# TIDM_TM4C129CAMERA.net
KiCad netlist of a schematic drawn in Altium Designer
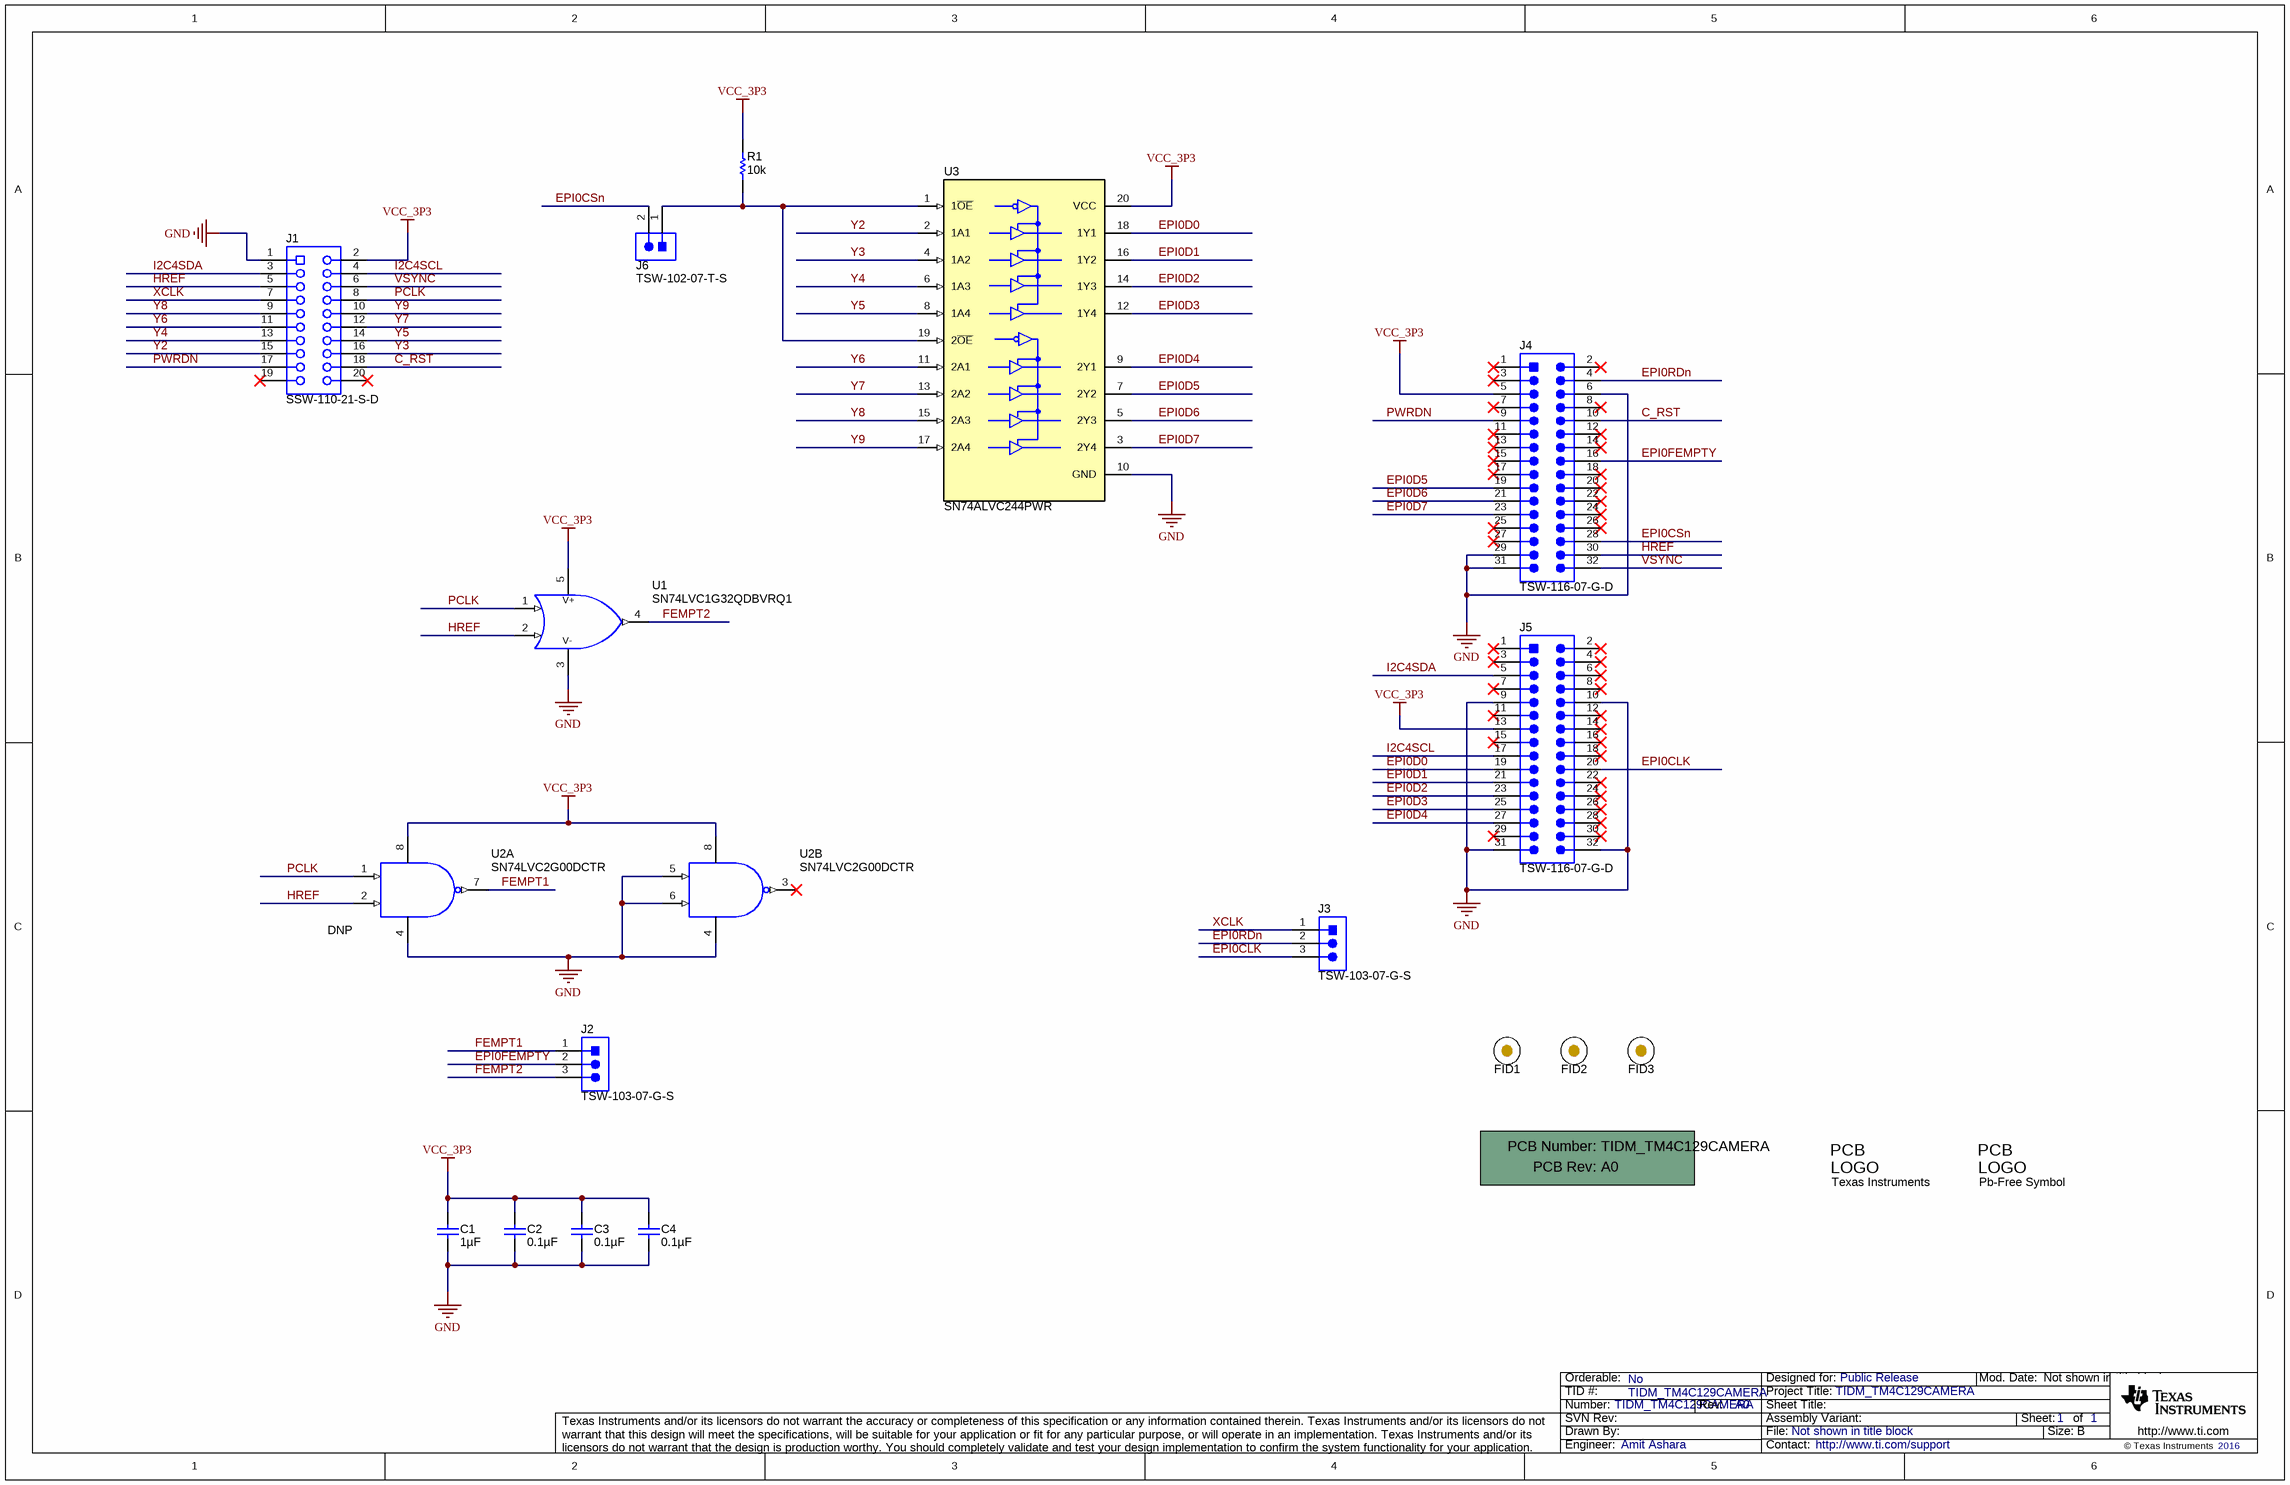
[diagram p0: TIDM_TM4C129CAMERA.SchDoc]

(export (version "E")
  (design (tool "Eeschema 10.0.6"))
  (components
    (comp (ref "!PCB")
      (value "Printed Circuit Board")
      (fields
        (field (name "MANUFACTURER") "Any")
        (field (name "SYMBOLCREATOR") "a0412235")
        (field (name "PUBLISHER") "Texas Instruments")
      )
      (libsource (lib "Hardware") (part "PCB"))
    )
    (comp (ref "C1")
      (value "GRM188R71A105KA61D")
      (footprint "0603")
      (description "CAP, CERM, 1 µF, 10 V, +/- 10%, X7R, 0603")
      (fields
        (field (name "VALUEDISPLAYED") "1µF")
        (field (name "MANUFACTURER") "MuRata")
        (field (name "PUBLISHER") "Texas Instruments")
      )
      (libsource (lib "Capacitor_Ceramic") (part "GRM188R71A105KA61D"))
    )
    (comp (ref "C2")
      (value "C0603C104K8RACTU")
      (footprint "0603")
      (description "CAP, CERM, 0.1 µF, 10 V, +/- 10%, X7R, 0603")
      (fields
        (field (name "VALUEDISPLAYED") "0.1µF")
        (field (name "MANUFACTURER") "Kemet")
        (field (name "PUBLISHER") "Texas Instruments")
      )
      (libsource (lib "Capacitor_Ceramic") (part "C0603C104K8RACTU"))
    )
    (comp (ref "C3")
      (value "C0603C104K8RACTU")
      (footprint "0603")
      (description "CAP, CERM, 0.1 µF, 10 V, +/- 10%, X7R, 0603")
      (fields
        (field (name "VALUEDISPLAYED") "0.1µF")
        (field (name "MANUFACTURER") "Kemet")
        (field (name "PUBLISHER") "Texas Instruments")
      )
      (libsource (lib "Capacitor_Ceramic") (part "C0603C104K8RACTU"))
    )
    (comp (ref "C4")
      (value "C0603C104K8RACTU")
      (footprint "0603")
      (description "CAP, CERM, 0.1 µF, 10 V, +/- 10%, X7R, 0603")
      (fields
        (field (name "VALUEDISPLAYED") "0.1µF")
        (field (name "MANUFACTURER") "Kemet")
        (field (name "PUBLISHER") "Texas Instruments")
      )
      (libsource (lib "Capacitor_Ceramic") (part "C0603C104K8RACTU"))
    )
    (comp (ref "FID1")
      (value "Fiducial")
      (footprint "Fiducial10-20")
      (description "Fiducial mark.  There is nothing to buy or mount.")
      (fields (field (name "SYMBOLCREATOR") "codlsc") (field (name "PUBLISHER") "Texas Instruments"))
      (libsource (lib "MiscParts") (part "Fiducial"))
    )
    (comp (ref "FID2")
      (value "Fiducial")
      (footprint "Fiducial10-20")
      (description "Fiducial mark.  There is nothing to buy or mount.")
      (fields (field (name "SYMBOLCREATOR") "codlsc") (field (name "PUBLISHER") "Texas Instruments"))
      (libsource (lib "MiscParts") (part "Fiducial"))
    )
    (comp (ref "FID3")
      (value "Fiducial")
      (footprint "Fiducial10-20")
      (description "Fiducial mark.  There is nothing to buy or mount.")
      (fields (field (name "SYMBOLCREATOR") "codlsc") (field (name "PUBLISHER") "Texas Instruments"))
      (libsource (lib "MiscParts") (part "Fiducial"))
    )
    (comp (ref "J1")
      (value "SSW-110-21-S-D")
      (footprint "Samtec_SSW-110-x1-x-D")
      (description "Receptacle, 2.54mm, 10x2, Gold, TH")
      (fields
        (field (name "MANUFACTURER") "Samtec")
        (field (name "SYMBOLCREATOR") "a0412235")
        (field (name "PUBLISHER") "Texas Instruments")
      )
      (libsource (lib "Connectors_Samtec") (part "SSW-110-21-S-D"))
    )
    (comp (ref "J2")
      (value "TSW-103-07-G-S")
      (footprint "TSW-103-07-G-S")
      (description "Header, 100mil, 3x1, Gold, TH")
      (fields
        (field (name "MANUFACTURER") "Samtec")
        (field (name "SYMBOLCREATOR") "a0799628")
        (field (name "PUBLISHER") "Texas Instruments")
      )
      (libsource (lib "Connectors_Samtec") (part "TSW-103-07-G-S"))
    )
    (comp (ref "J3")
      (value "TSW-103-07-G-S")
      (footprint "TSW-103-07-G-S")
      (description "Header, 100mil, 3x1, Gold, TH")
      (fields
        (field (name "MANUFACTURER") "Samtec")
        (field (name "SYMBOLCREATOR") "a0799628")
        (field (name "PUBLISHER") "Texas Instruments")
      )
      (libsource (lib "Connectors_Samtec") (part "TSW-103-07-G-S"))
    )
    (comp (ref "J4")
      (value "TSW-116-07-G-D")
      (footprint "TSW-116-07-G-D")
      (description "Header, 100mil, 16x2, Gold, TH")
      (fields
        (field (name "MANUFACTURER") "Samtec")
        (field (name "SYMBOLCREATOR") "a0412235")
        (field (name "PUBLISHER") "Texas Instruments")
      )
      (libsource (lib "Connectors_Samtec") (part "TSW-116-07-G-D"))
    )
    (comp (ref "J5")
      (value "TSW-116-07-G-D")
      (footprint "TSW-116-07-G-D")
      (description "Header, 100mil, 16x2, Gold, TH")
      (fields
        (field (name "MANUFACTURER") "Samtec")
        (field (name "SYMBOLCREATOR") "a0412235")
        (field (name "PUBLISHER") "Texas Instruments")
      )
      (libsource (lib "Connectors_Samtec") (part "TSW-116-07-G-D"))
    )
    (comp (ref "J6")
      (value "TSW-102-07-T-S")
      (footprint "Samtec_TSW-102-07-T-S")
      (description "Header, 2.54 mm, 2x1, Tin, TH")
      (fields
        (field (name "MANUFACTURER") "Samtec")
        (field (name "SYMBOLCREATOR") "a0412235")
        (field (name "PUBLISHER") "Texas Instruments")
      )
      (libsource (lib "Connectors_Samtec") (part "TSW-102-07-T-S"))
    )
    (comp (ref "Logo1")
      (value "Texas Instruments")
      (footprint "TI_Stacked_Overlay_Small")
      (description "Texas Instrument Corporate Signature")
      (fields (field (name "SYMBOLCREATOR") "codlsc") (field (name "PUBLISHER") "National Semiconductor"))
      (libsource (lib "Logos") (part "TI_Logo"))
    )
    (comp (ref "Logo2")
      (value "Pb-Free Symbol")
      (footprint "Pb-Free_Overlay_Small")
      (fields (field (name "SYMBOLCREATOR") "a0412235") (field (name "PUBLISHER") "Texas Instruments"))
      (libsource (lib "Logos") (part "Pb-Free"))
    )
    (comp (ref "R1")
      (value "CRCW060310K0JNEA")
      (footprint "0603")
      (description "RES, 10 k, 5%, 0.1 W, 0603")
      (fields
        (field (name "VALUEDISPLAYED") "10k")
        (field (name "MANUFACTURER") "Vishay-Dale")
        (field (name "PUBLISHER") "Texas Instruments")
      )
      (libsource (lib "Resistor_0603") (part "CRCW060310K0JNEA"))
    )
    (comp (ref "U1")
      (value "SN74LVC1G32QDBVRQ1")
      (footprint "DBV0005A_N")
      (description "SINGLE 2-INPUT POSITIVE-OR GATE, DBV0005A")
      (fields
        (field (name "MANUFACTURER") "Texas Instruments")
        (field (name "SYMBOLCREATOR") "a0411947")
        (field (name "PUBLISHER") "Texas Instruments")
      )
      (libsource (lib "TI_Pre_Release") (part "SN74LVC1G32QDBVRQ1"))
    )
    (comp (ref "U2")
      (value "SN74LVC2G00DCTR")
      (footprint "DCT0008A_N")
      (description "Dual 2-Input Positive-NAND Gate, DCT0008A")
      (fields
        (field (name "MANUFACTURER") "Texas Instruments")
        (field (name "SYMBOLCREATOR") "a0411947")
        (field (name "PUBLISHER") "Texas Instruments")
      )
      (libsource (lib "TI_Pre_Release") (part "SN74LVC2G00DCTR"))
    )
    (comp (ref "U3")
      (value "SN74ALVC244PWR")
      (footprint "PW0020A_N")
      (description "OCTAL BUFFER/DRIVER WITH 3-STATE OUTPUTS, PW0020A")
      (fields
        (field (name "ALTERNATE PARTNUMBER") "SN74ALVC244PW")
        (field (name "MANUFACTURER") "Texas Instruments")
        (field (name "SYMBOLCREATOR") "Altium")
        (field (name "PUBLISHER") "Texas Instruments")
      )
      (libsource (lib "TI_Pre_Release1") (part "SN74ALVC244PWR"))
    )
  )
  (nets
    (net (code "1") (name "/C_RST") (class "Default")
      (node (ref "J1") (pin "18") (pinfunction "18_18") (pintype "passive"))
      (node (ref "J4") (pin "10") (pinfunction "10_10") (pintype "passive"))
    )
    (net (code "2") (name "/EPI0CLK") (class "Default")
      (node (ref "J3") (pin "3") (pinfunction "3_3") (pintype "passive"))
      (node (ref "J5") (pin "20") (pinfunction "20_20") (pintype "passive"))
    )
    (net (code "3") (name "/EPI0CSn") (class "Default")
      (node (ref "J4") (pin "28") (pinfunction "28_28") (pintype "passive"))
      (node (ref "J6") (pin "2") (pinfunction "2_2") (pintype "passive"))
    )
    (net (code "4") (name "/EPI0D0") (class "Default")
      (node (ref "J5") (pin "19") (pinfunction "19_19") (pintype "passive"))
      (node (ref "U3") (pin "18") (pinfunction "1Y1_18") (pintype "tri_state"))
    )
    (net (code "5") (name "/EPI0D1") (class "Default")
      (node (ref "J5") (pin "21") (pinfunction "21_21") (pintype "passive"))
      (node (ref "U3") (pin "16") (pinfunction "1Y2_16") (pintype "tri_state"))
    )
    (net (code "6") (name "/EPI0D2") (class "Default")
      (node (ref "J5") (pin "23") (pinfunction "23_23") (pintype "passive"))
      (node (ref "U3") (pin "14") (pinfunction "1Y3_14") (pintype "tri_state"))
    )
    (net (code "7") (name "/EPI0D3") (class "Default")
      (node (ref "J5") (pin "25") (pinfunction "25_25") (pintype "passive"))
      (node (ref "U3") (pin "12") (pinfunction "1Y4_12") (pintype "tri_state"))
    )
    (net (code "8") (name "/EPI0D4") (class "Default")
      (node (ref "J5") (pin "27") (pinfunction "27_27") (pintype "passive"))
      (node (ref "U3") (pin "9") (pinfunction "2Y1_9") (pintype "tri_state"))
    )
    (net (code "9") (name "/EPI0D5") (class "Default")
      (node (ref "J4") (pin "19") (pinfunction "19_19") (pintype "passive"))
      (node (ref "U3") (pin "7") (pinfunction "2Y2_7") (pintype "tri_state"))
    )
    (net (code "10") (name "/EPI0D6") (class "Default")
      (node (ref "J4") (pin "21") (pinfunction "21_21") (pintype "passive"))
      (node (ref "U3") (pin "5") (pinfunction "2Y3_5") (pintype "tri_state"))
    )
    (net (code "11") (name "/EPI0D7") (class "Default")
      (node (ref "J4") (pin "23") (pinfunction "23_23") (pintype "passive"))
      (node (ref "U3") (pin "3") (pinfunction "2Y4_3") (pintype "tri_state"))
    )
    (net (code "12") (name "/EPI0FEMPTY") (class "Default")
      (node (ref "J2") (pin "2") (pinfunction "2_2") (pintype "passive"))
      (node (ref "J4") (pin "16") (pinfunction "16_16") (pintype "passive"))
    )
    (net (code "13") (name "/EPI0RDn") (class "Default")
      (node (ref "J3") (pin "2") (pinfunction "2_2") (pintype "passive"))
      (node (ref "J4") (pin "4") (pinfunction "4_4") (pintype "passive"))
    )
    (net (code "14") (name "/FEMPT1") (class "Default")
      (node (ref "J2") (pin "1") (pinfunction "1_1") (pintype "passive"))
      (node (ref "U2") (pin "7") (pinfunction "1Y_7") (pintype "output"))
    )
    (net (code "15") (name "/FEMPT2") (class "Default")
      (node (ref "J2") (pin "3") (pinfunction "3_3") (pintype "passive"))
      (node (ref "U1") (pin "4") (pinfunction "Y_4") (pintype "output"))
    )
    (net (code "16") (name "/HREF") (class "Default")
      (node (ref "J1") (pin "5") (pinfunction "5_5") (pintype "passive"))
      (node (ref "J4") (pin "30") (pinfunction "30_30") (pintype "passive"))
      (node (ref "U1") (pin "2") (pinfunction "B_2") (pintype "input"))
      (node (ref "U2") (pin "2") (pinfunction "1B_2") (pintype "input"))
    )
    (net (code "17") (name "/I2C4SCL") (class "Default")
      (node (ref "J1") (pin "4") (pinfunction "4_4") (pintype "passive"))
      (node (ref "J5") (pin "17") (pinfunction "17_17") (pintype "passive"))
    )
    (net (code "18") (name "/I2C4SDA") (class "Default")
      (node (ref "J1") (pin "3") (pinfunction "3_3") (pintype "passive"))
      (node (ref "J5") (pin "5") (pinfunction "5_5") (pintype "passive"))
    )
    (net (code "19") (name "/PCLK") (class "Default")
      (node (ref "J1") (pin "8") (pinfunction "8_8") (pintype "passive"))
      (node (ref "U1") (pin "1") (pinfunction "A_1") (pintype "input"))
      (node (ref "U2") (pin "1") (pinfunction "1A_1") (pintype "input"))
    )
    (net (code "20") (name "/PWRDN") (class "Default")
      (node (ref "J1") (pin "17") (pinfunction "17_17") (pintype "passive"))
      (node (ref "J4") (pin "9") (pinfunction "9_9") (pintype "passive"))
    )
    (net (code "21") (name "/VSYNC") (class "Default")
      (node (ref "J1") (pin "6") (pinfunction "6_6") (pintype "passive"))
      (node (ref "J4") (pin "32") (pinfunction "32_32") (pintype "passive"))
    )
    (net (code "22") (name "/XCLK") (class "Default")
      (node (ref "J1") (pin "7") (pinfunction "7_7") (pintype "passive"))
      (node (ref "J3") (pin "1") (pinfunction "1_1") (pintype "passive"))
    )
    (net (code "23") (name "/Y2") (class "Default")
      (node (ref "J1") (pin "15") (pinfunction "15_15") (pintype "passive"))
      (node (ref "U3") (pin "2") (pinfunction "1A1_2") (pintype "input"))
    )
    (net (code "24") (name "/Y3") (class "Default")
      (node (ref "J1") (pin "16") (pinfunction "16_16") (pintype "passive"))
      (node (ref "U3") (pin "4") (pinfunction "1A2_4") (pintype "input"))
    )
    (net (code "25") (name "/Y4") (class "Default")
      (node (ref "J1") (pin "13") (pinfunction "13_13") (pintype "passive"))
      (node (ref "U3") (pin "6") (pinfunction "1A3_6") (pintype "input"))
    )
    (net (code "26") (name "/Y5") (class "Default")
      (node (ref "J1") (pin "14") (pinfunction "14_14") (pintype "passive"))
      (node (ref "U3") (pin "8") (pinfunction "1A4_8") (pintype "input"))
    )
    (net (code "27") (name "/Y6") (class "Default")
      (node (ref "J1") (pin "11") (pinfunction "11_11") (pintype "passive"))
      (node (ref "U3") (pin "11") (pinfunction "2A1_11") (pintype "input"))
    )
    (net (code "28") (name "/Y7") (class "Default")
      (node (ref "J1") (pin "12") (pinfunction "12_12") (pintype "passive"))
      (node (ref "U3") (pin "13") (pinfunction "2A2_13") (pintype "input"))
    )
    (net (code "29") (name "/Y8") (class "Default")
      (node (ref "J1") (pin "9") (pinfunction "9_9") (pintype "passive"))
      (node (ref "U3") (pin "15") (pinfunction "2A3_15") (pintype "input"))
    )
    (net (code "30") (name "/Y9") (class "Default")
      (node (ref "J1") (pin "10") (pinfunction "10_10") (pintype "passive"))
      (node (ref "U3") (pin "17") (pinfunction "2A4_17") (pintype "input"))
    )
    (net (code "31") (name "GND") (class "Default")
      (node (ref "C1") (pin "2") (pinfunction "2_2") (pintype "passive"))
      (node (ref "C2") (pin "2") (pinfunction "2_2") (pintype "passive"))
      (node (ref "C3") (pin "2") (pinfunction "2_2") (pintype "passive"))
      (node (ref "C4") (pin "2") (pinfunction "2_2") (pintype "passive"))
      (node (ref "J1") (pin "1") (pinfunction "1_1") (pintype "passive"))
      (node (ref "J4") (pin "29") (pinfunction "29_29") (pintype "passive"))
      (node (ref "J4") (pin "31") (pinfunction "31_31") (pintype "passive"))
      (node (ref "J4") (pin "6") (pinfunction "6_6") (pintype "passive"))
      (node (ref "J5") (pin "10") (pinfunction "10_10") (pintype "passive"))
      (node (ref "J5") (pin "31") (pinfunction "31_31") (pintype "passive"))
      (node (ref "J5") (pin "32") (pinfunction "32_32") (pintype "passive"))
      (node (ref "J5") (pin "9") (pinfunction "9_9") (pintype "passive"))
      (node (ref "U1") (pin "3") (pinfunction "GND_3") (pintype "power_in"))
      (node (ref "U2") (pin "4") (pinfunction "GND_4") (pintype "power_in"))
      (node (ref "U2") (pin "5") (pinfunction "2A_5") (pintype "input"))
      (node (ref "U2") (pin "6") (pinfunction "2B_6") (pintype "input"))
      (node (ref "U3") (pin "10") (pinfunction "GND_10") (pintype "power_in"))
    )
    (net (code "32") (name "Net-(U3-1~{OE})") (class "Default")
      (node (ref "J6") (pin "1") (pinfunction "1_1") (pintype "passive"))
      (node (ref "R1") (pin "1") (pinfunction "1_1") (pintype "passive"))
      (node (ref "U3") (pin "1") (pinfunction "1~{OE}_1") (pintype "input"))
      (node (ref "U3") (pin "19") (pinfunction "2~{OE}_19") (pintype "input"))
    )
    (net (code "33") (name "VCC_3P3") (class "Default")
      (node (ref "C1") (pin "1") (pinfunction "1_1") (pintype "passive"))
      (node (ref "C2") (pin "1") (pinfunction "1_1") (pintype "passive"))
      (node (ref "C3") (pin "1") (pinfunction "1_1") (pintype "passive"))
      (node (ref "C4") (pin "1") (pinfunction "1_1") (pintype "passive"))
      (node (ref "J1") (pin "2") (pinfunction "2_2") (pintype "passive"))
      (node (ref "J4") (pin "5") (pinfunction "5_5") (pintype "passive"))
      (node (ref "J5") (pin "13") (pinfunction "13_13") (pintype "passive"))
      (node (ref "R1") (pin "2") (pinfunction "2_2") (pintype "passive"))
      (node (ref "U1") (pin "5") (pinfunction "VCC_5") (pintype "power_in"))
      (node (ref "U2") (pin "8") (pinfunction "VCC_8") (pintype "power_in"))
      (node (ref "U3") (pin "20") (pinfunction "VCC_20") (pintype "power_in"))
    )
    (net (code "34") (name "unconnected-(J1-Pad19)") (class "Default")
      (node (ref "J1") (pin "19") (pinfunction "19_19") (pintype "passive+no_connect"))
    )
    (net (code "35") (name "unconnected-(J1-Pad20)") (class "Default")
      (node (ref "J1") (pin "20") (pinfunction "20_20") (pintype "passive+no_connect"))
    )
    (net (code "36") (name "unconnected-(J4-Pad1)") (class "Default")
      (node (ref "J4") (pin "1") (pinfunction "1_1") (pintype "passive+no_connect"))
    )
    (net (code "37") (name "unconnected-(J4-Pad2)") (class "Default")
      (node (ref "J4") (pin "2") (pinfunction "2_2") (pintype "passive+no_connect"))
    )
    (net (code "38") (name "unconnected-(J4-Pad3)") (class "Default")
      (node (ref "J4") (pin "3") (pinfunction "3_3") (pintype "passive+no_connect"))
    )
    (net (code "39") (name "unconnected-(J4-Pad7)") (class "Default")
      (node (ref "J4") (pin "7") (pinfunction "7_7") (pintype "passive+no_connect"))
    )
    (net (code "40") (name "unconnected-(J4-Pad8)") (class "Default")
      (node (ref "J4") (pin "8") (pinfunction "8_8") (pintype "passive+no_connect"))
    )
    (net (code "41") (name "unconnected-(J4-Pad11)") (class "Default")
      (node (ref "J4") (pin "11") (pinfunction "11_11") (pintype "passive+no_connect"))
    )
    (net (code "42") (name "unconnected-(J4-Pad12)") (class "Default")
      (node (ref "J4") (pin "12") (pinfunction "12_12") (pintype "passive+no_connect"))
    )
    (net (code "43") (name "unconnected-(J4-Pad13)") (class "Default")
      (node (ref "J4") (pin "13") (pinfunction "13_13") (pintype "passive+no_connect"))
    )
    (net (code "44") (name "unconnected-(J4-Pad14)") (class "Default")
      (node (ref "J4") (pin "14") (pinfunction "14_14") (pintype "passive+no_connect"))
    )
    (net (code "45") (name "unconnected-(J4-Pad15)") (class "Default")
      (node (ref "J4") (pin "15") (pinfunction "15_15") (pintype "passive+no_connect"))
    )
    (net (code "46") (name "unconnected-(J4-Pad17)") (class "Default")
      (node (ref "J4") (pin "17") (pinfunction "17_17") (pintype "passive+no_connect"))
    )
    (net (code "47") (name "unconnected-(J4-Pad18)") (class "Default")
      (node (ref "J4") (pin "18") (pinfunction "18_18") (pintype "passive+no_connect"))
    )
    (net (code "48") (name "unconnected-(J4-Pad20)") (class "Default")
      (node (ref "J4") (pin "20") (pinfunction "20_20") (pintype "passive+no_connect"))
    )
    (net (code "49") (name "unconnected-(J4-Pad22)") (class "Default")
      (node (ref "J4") (pin "22") (pinfunction "22_22") (pintype "passive+no_connect"))
    )
    (net (code "50") (name "unconnected-(J4-Pad24)") (class "Default")
      (node (ref "J4") (pin "24") (pinfunction "24_24") (pintype "passive+no_connect"))
    )
    (net (code "51") (name "unconnected-(J4-Pad25)") (class "Default")
      (node (ref "J4") (pin "25") (pinfunction "25_25") (pintype "passive+no_connect"))
    )
    (net (code "52") (name "unconnected-(J4-Pad26)") (class "Default")
      (node (ref "J4") (pin "26") (pinfunction "26_26") (pintype "passive+no_connect"))
    )
    (net (code "53") (name "unconnected-(J4-Pad27)") (class "Default")
      (node (ref "J4") (pin "27") (pinfunction "27_27") (pintype "passive+no_connect"))
    )
    (net (code "54") (name "unconnected-(J5-Pad1)") (class "Default")
      (node (ref "J5") (pin "1") (pinfunction "1_1") (pintype "passive+no_connect"))
    )
    (net (code "55") (name "unconnected-(J5-Pad2)") (class "Default")
      (node (ref "J5") (pin "2") (pinfunction "2_2") (pintype "passive+no_connect"))
    )
    (net (code "56") (name "unconnected-(J5-Pad3)") (class "Default")
      (node (ref "J5") (pin "3") (pinfunction "3_3") (pintype "passive+no_connect"))
    )
    (net (code "57") (name "unconnected-(J5-Pad4)") (class "Default")
      (node (ref "J5") (pin "4") (pinfunction "4_4") (pintype "passive+no_connect"))
    )
    (net (code "58") (name "unconnected-(J5-Pad6)") (class "Default")
      (node (ref "J5") (pin "6") (pinfunction "6_6") (pintype "passive+no_connect"))
    )
    (net (code "59") (name "unconnected-(J5-Pad7)") (class "Default")
      (node (ref "J5") (pin "7") (pinfunction "7_7") (pintype "passive+no_connect"))
    )
    (net (code "60") (name "unconnected-(J5-Pad8)") (class "Default")
      (node (ref "J5") (pin "8") (pinfunction "8_8") (pintype "passive+no_connect"))
    )
    (net (code "61") (name "unconnected-(J5-Pad11)") (class "Default")
      (node (ref "J5") (pin "11") (pinfunction "11_11") (pintype "passive+no_connect"))
    )
    (net (code "62") (name "unconnected-(J5-Pad12)") (class "Default")
      (node (ref "J5") (pin "12") (pinfunction "12_12") (pintype "passive+no_connect"))
    )
    (net (code "63") (name "unconnected-(J5-Pad14)") (class "Default")
      (node (ref "J5") (pin "14") (pinfunction "14_14") (pintype "passive+no_connect"))
    )
    (net (code "64") (name "unconnected-(J5-Pad15)") (class "Default")
      (node (ref "J5") (pin "15") (pinfunction "15_15") (pintype "passive+no_connect"))
    )
    (net (code "65") (name "unconnected-(J5-Pad16)") (class "Default")
      (node (ref "J5") (pin "16") (pinfunction "16_16") (pintype "passive+no_connect"))
    )
    (net (code "66") (name "unconnected-(J5-Pad18)") (class "Default")
      (node (ref "J5") (pin "18") (pinfunction "18_18") (pintype "passive+no_connect"))
    )
    (net (code "67") (name "unconnected-(J5-Pad22)") (class "Default")
      (node (ref "J5") (pin "22") (pinfunction "22_22") (pintype "passive+no_connect"))
    )
    (net (code "68") (name "unconnected-(J5-Pad24)") (class "Default")
      (node (ref "J5") (pin "24") (pinfunction "24_24") (pintype "passive+no_connect"))
    )
    (net (code "69") (name "unconnected-(J5-Pad26)") (class "Default")
      (node (ref "J5") (pin "26") (pinfunction "26_26") (pintype "passive+no_connect"))
    )
    (net (code "70") (name "unconnected-(J5-Pad28)") (class "Default")
      (node (ref "J5") (pin "28") (pinfunction "28_28") (pintype "passive+no_connect"))
    )
    (net (code "71") (name "unconnected-(J5-Pad29)") (class "Default")
      (node (ref "J5") (pin "29") (pinfunction "29_29") (pintype "passive+no_connect"))
    )
    (net (code "72") (name "unconnected-(J5-Pad30)") (class "Default")
      (node (ref "J5") (pin "30") (pinfunction "30_30") (pintype "passive+no_connect"))
    )
    (net (code "73") (name "unconnected-(U2B-2Y-Pad3)") (class "Default")
      (node (ref "U2") (pin "3") (pinfunction "2Y_3") (pintype "output+no_connect"))
    )
  )
)
